# Debug.net
KiCad netlist of a schematic drawn in Altium Designer
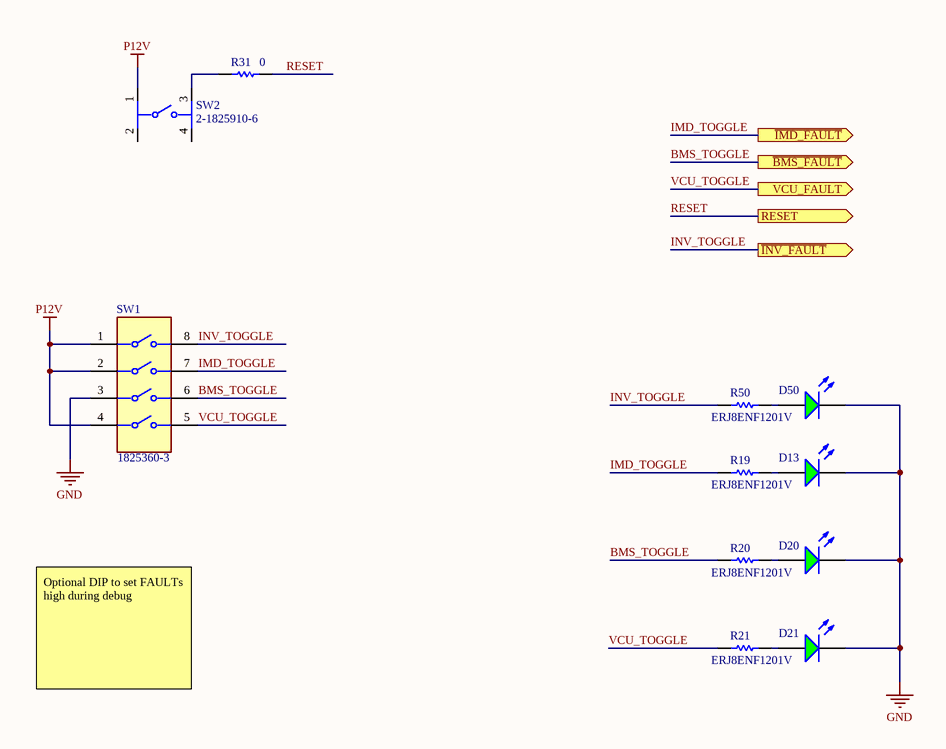
[diagram p0:  Debug.SchDoc]

(export (version "E")
  (design (tool "Eeschema 10.0.6"))
  (components
    (comp (ref "D13")
      (value "597-3311-407F")
      (footprint "DIAL-597-3311-407F_V")
      (description "LED Green, 75 mW, 30 mA, -30 to 85 degC, 2-Pin SMD, RoHS, Tape and Reel")
      (fields (field (name "MANUFACTURER") "Dialight"))
      (libsource (lib "Altium Content Vault") (part "LED-GREEN-AK-2"))
    )
    (comp (ref "D20")
      (value "597-3311-407F")
      (footprint "DIAL-597-3311-407F_V")
      (description "LED Green, 75 mW, 30 mA, -30 to 85 degC, 2-Pin SMD, RoHS, Tape and Reel")
      (fields (field (name "MANUFACTURER") "Dialight"))
      (libsource (lib "Altium Content Vault") (part "LED-GREEN-AK-2"))
    )
    (comp (ref "D21")
      (value "597-3311-407F")
      (footprint "DIAL-597-3311-407F_V")
      (description "LED Green, 75 mW, 30 mA, -30 to 85 degC, 2-Pin SMD, RoHS, Tape and Reel")
      (fields (field (name "MANUFACTURER") "Dialight"))
      (libsource (lib "Altium Content Vault") (part "LED-GREEN-AK-2"))
    )
    (comp (ref "D50")
      (value "597-3311-407F")
      (footprint "DIAL-597-3311-407F_V")
      (description "LED Green, 75 mW, 30 mA, -30 to 85 degC, 2-Pin SMD, RoHS, Tape and Reel")
      (fields (field (name "MANUFACTURER") "Dialight"))
      (libsource (lib "Altium Content Vault") (part "LED-GREEN-AK-2"))
    )
    (comp (ref "R19")
      (value "ERJ8ENF1201V")
      (footprint "RESC3216X70X50LL05T20")
      (fields (field (name "MANUFACTURER") "Panasonic"))
      (libsource (lib "Altium Content Vault") (part "RES"))
    )
    (comp (ref "R20")
      (value "ERJ8ENF1201V")
      (footprint "RESC3216X70X50LL05T20")
      (fields (field (name "MANUFACTURER") "Panasonic"))
      (libsource (lib "Altium Content Vault") (part "RES"))
    )
    (comp (ref "R21")
      (value "ERJ8ENF1201V")
      (footprint "RESC3216X70X50LL05T20")
      (fields (field (name "MANUFACTURER") "Panasonic"))
      (libsource (lib "Altium Content Vault") (part "RES"))
    )
    (comp (ref "R31")
      (value "0")
      (footprint "RESC3216X60X45ML15T20")
      (description "Chip Resistor, 0 Ohm, +/- 5%, 0.25 W, -55 to 155 degC, 1206 (3216 Metric)")
      (fields (field (name "POWER") "250mW") (field (name "TOLERANCE") "5%"))
      (libsource (lib "University of California Riverside - FSAE") (part "RES-2"))
    )
    (comp (ref "R50")
      (value "ERJ8ENF1201V")
      (footprint "RESC3216X70X50LL05T20")
      (fields (field (name "MANUFACTURER") "Panasonic"))
      (libsource (lib "Altium Content Vault") (part "RES"))
    )
    (comp (ref "SW1")
      (value "1825360-3")
      (footprint "FP-1825360-3-MFG")
      (description "SWITCH SLIDE DIP SPST 100MA 24V")
      (libsource (lib "Altium Content Vault") (part "8a6f13ad003845d0737bd9d25158ffb"))
    )
    (comp (ref "SW2")
      (value "2-1825910-6")
      (footprint "FP-2-1825910-6-MFG")
      (description "SWITCH TACTILE SPST-NO 0.05A 24V")
      (libsource (lib "Altium Content Vault") (part "b8895f3f4cefb76e1819d2863dba89b"))
    )
  )
  (nets
    (net (code "1") (name "/BMS_TOGGLE") (class "Default")
      (node (ref "R20") (pin "1") (pinfunction "1_1") (pintype "passive"))
      (node (ref "SW1") (pin "6") (pinfunction "6_6") (pintype "passive"))
    )
    (net (code "2") (name "/IMD_TOGGLE") (class "Default")
      (node (ref "R19") (pin "1") (pinfunction "1_1") (pintype "passive"))
      (node (ref "SW1") (pin "7") (pinfunction "7_7") (pintype "passive"))
    )
    (net (code "3") (name "/INV_TOGGLE") (class "Default")
      (node (ref "R50") (pin "1") (pinfunction "1_1") (pintype "passive"))
      (node (ref "SW1") (pin "8") (pinfunction "8_8") (pintype "passive"))
    )
    (net (code "4") (name "/RESET") (class "Default")
      (node (ref "R31") (pin "2") (pinfunction "2_2") (pintype "passive"))
    )
    (net (code "5") (name "/VCU_TOGGLE") (class "Default")
      (node (ref "R21") (pin "1") (pinfunction "1_1") (pintype "passive"))
      (node (ref "SW1") (pin "5") (pinfunction "5_5") (pintype "passive"))
    )
    (net (code "6") (name "GND") (class "Default")
      (node (ref "D13") (pin "2") (pinfunction "K_2") (pintype "passive"))
      (node (ref "D20") (pin "2") (pinfunction "K_2") (pintype "passive"))
      (node (ref "D21") (pin "2") (pinfunction "K_2") (pintype "passive"))
      (node (ref "D50") (pin "2") (pinfunction "K_2") (pintype "passive"))
      (node (ref "SW1") (pin "3") (pinfunction "3_3") (pintype "passive"))
    )
    (net (code "7") (name "Net-(D13-A)") (class "Default")
      (node (ref "D13") (pin "1") (pinfunction "A_1") (pintype "passive"))
      (node (ref "R19") (pin "2") (pinfunction "2_2") (pintype "passive"))
    )
    (net (code "8") (name "Net-(D20-A)") (class "Default")
      (node (ref "D20") (pin "1") (pinfunction "A_1") (pintype "passive"))
      (node (ref "R20") (pin "2") (pinfunction "2_2") (pintype "passive"))
    )
    (net (code "9") (name "Net-(D21-A)") (class "Default")
      (node (ref "D21") (pin "1") (pinfunction "A_1") (pintype "passive"))
      (node (ref "R21") (pin "2") (pinfunction "2_2") (pintype "passive"))
    )
    (net (code "10") (name "Net-(D50-A)") (class "Default")
      (node (ref "D50") (pin "1") (pinfunction "A_1") (pintype "passive"))
      (node (ref "R50") (pin "2") (pinfunction "2_2") (pintype "passive"))
    )
    (net (code "11") (name "Net-(R31-Pad1)") (class "Default")
      (node (ref "R31") (pin "1") (pinfunction "1_1") (pintype "passive"))
      (node (ref "SW2") (pin "3") (pinfunction "3_3") (pintype "passive"))
    )
    (net (code "12") (name "P12V") (class "Default")
      (node (ref "SW1") (pin "1") (pinfunction "1_1") (pintype "passive"))
      (node (ref "SW1") (pin "2") (pinfunction "2_2") (pintype "passive"))
      (node (ref "SW1") (pin "4") (pinfunction "4_4") (pintype "passive"))
      (node (ref "SW2") (pin "1") (pinfunction "1_1") (pintype "passive"))
    )
    (net (code "13") (name "unconnected-(SW2-Pad2)") (class "Default")
      (node (ref "SW2") (pin "2") (pinfunction "2_2") (pintype "passive"))
    )
    (net (code "14") (name "unconnected-(SW2-Pad4)") (class "Default")
      (node (ref "SW2") (pin "4") (pinfunction "4_4") (pintype "passive"))
    )
  )
)
